# voltage_converter.net
KiCad netlist of a schematic drawn in EAGLE
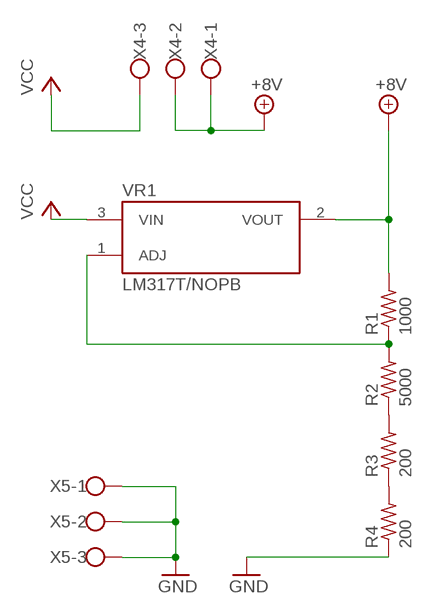
[diagram p0: schematic, sheet 1]

(export (version "E")
  (design (tool "Eeschema 10.0.6"))
  (components
    (comp (ref "R1")
      (value "1000")
      (footprint "eagle-import:0204_5")
      (libsource (lib "eagle-import") (part "R-US_0204/5"))
    )
    (comp (ref "R2")
      (value "5000")
      (footprint "eagle-import:0204_5")
      (libsource (lib "eagle-import") (part "R-US_0204/5"))
    )
    (comp (ref "R3")
      (value "200")
      (footprint "eagle-import:0204_5")
      (libsource (lib "eagle-import") (part "R-US_0204/5"))
    )
    (comp (ref "R4")
      (value "200")
      (footprint "eagle-import:0204_5")
      (libsource (lib "eagle-import") (part "R-US_0204/5"))
    )
    (comp (ref "VR1")
      (value "LM317T/NOPB")
      (footprint "eagle-import:TO254P1054X470X1955-3")
      (fields (field (name "MF") "Texas Instruments"))
      (libsource (lib "eagle-import") (part "LM317T/NOPB"))
    )
    (comp (ref "X4")
      (value "W237-103")
      (footprint "eagle-import:W237-103")
      (fields (field (name "MPN") "237-103"))
      (libsource (lib "eagle-import") (part "W237-103"))
    )
    (comp (ref "X5")
      (value "W237-103")
      (footprint "eagle-import:W237-103")
      (fields (field (name "MPN") "237-103"))
      (libsource (lib "eagle-import") (part "W237-103"))
    )
  )
  (nets
    (net (code "1") (name "+8V") (class "Default")
      (node (ref "R1") (pin "2") (pinfunction "2_2") (pintype "passive"))
      (node (ref "VR1") (pin "2") (pinfunction "VOUT_2") (pintype "output"))
      (node (ref "X4") (pin "1") (pinfunction "KL_1") (pintype "passive"))
      (node (ref "X4") (pin "2") (pinfunction "KL_2") (pintype "passive"))
    )
    (net (code "2") (name "GND") (class "Default")
      (node (ref "R4") (pin "1") (pinfunction "1_1") (pintype "passive"))
      (node (ref "X5") (pin "1") (pinfunction "KL_1") (pintype "passive"))
      (node (ref "X5") (pin "2") (pinfunction "KL_2") (pintype "passive"))
      (node (ref "X5") (pin "3") (pinfunction "KL_3") (pintype "passive"))
    )
    (net (code "3") (name "Net-(R2-Pad1)") (class "Default")
      (node (ref "R2") (pin "1") (pinfunction "1_1") (pintype "passive"))
      (node (ref "R3") (pin "2") (pinfunction "2_2") (pintype "passive"))
    )
    (net (code "4") (name "Net-(R3-Pad1)") (class "Default")
      (node (ref "R3") (pin "1") (pinfunction "1_1") (pintype "passive"))
      (node (ref "R4") (pin "2") (pinfunction "2_2") (pintype "passive"))
    )
    (net (code "5") (name "Net-(VR1-ADJ)") (class "Default")
      (node (ref "R1") (pin "1") (pinfunction "1_1") (pintype "passive"))
      (node (ref "R2") (pin "2") (pinfunction "2_2") (pintype "passive"))
      (node (ref "VR1") (pin "1") (pinfunction "ADJ_1") (pintype "passive"))
    )
    (net (code "6") (name "VCC") (class "Default")
      (node (ref "VR1") (pin "3") (pinfunction "VIN_3") (pintype "input"))
      (node (ref "X4") (pin "3") (pinfunction "KL_3") (pintype "passive"))
    )
  )
)
